# SCH_Static-stand-for-thrust-and-torque.net
KiCad netlist of a schematic drawn in EasyEDA
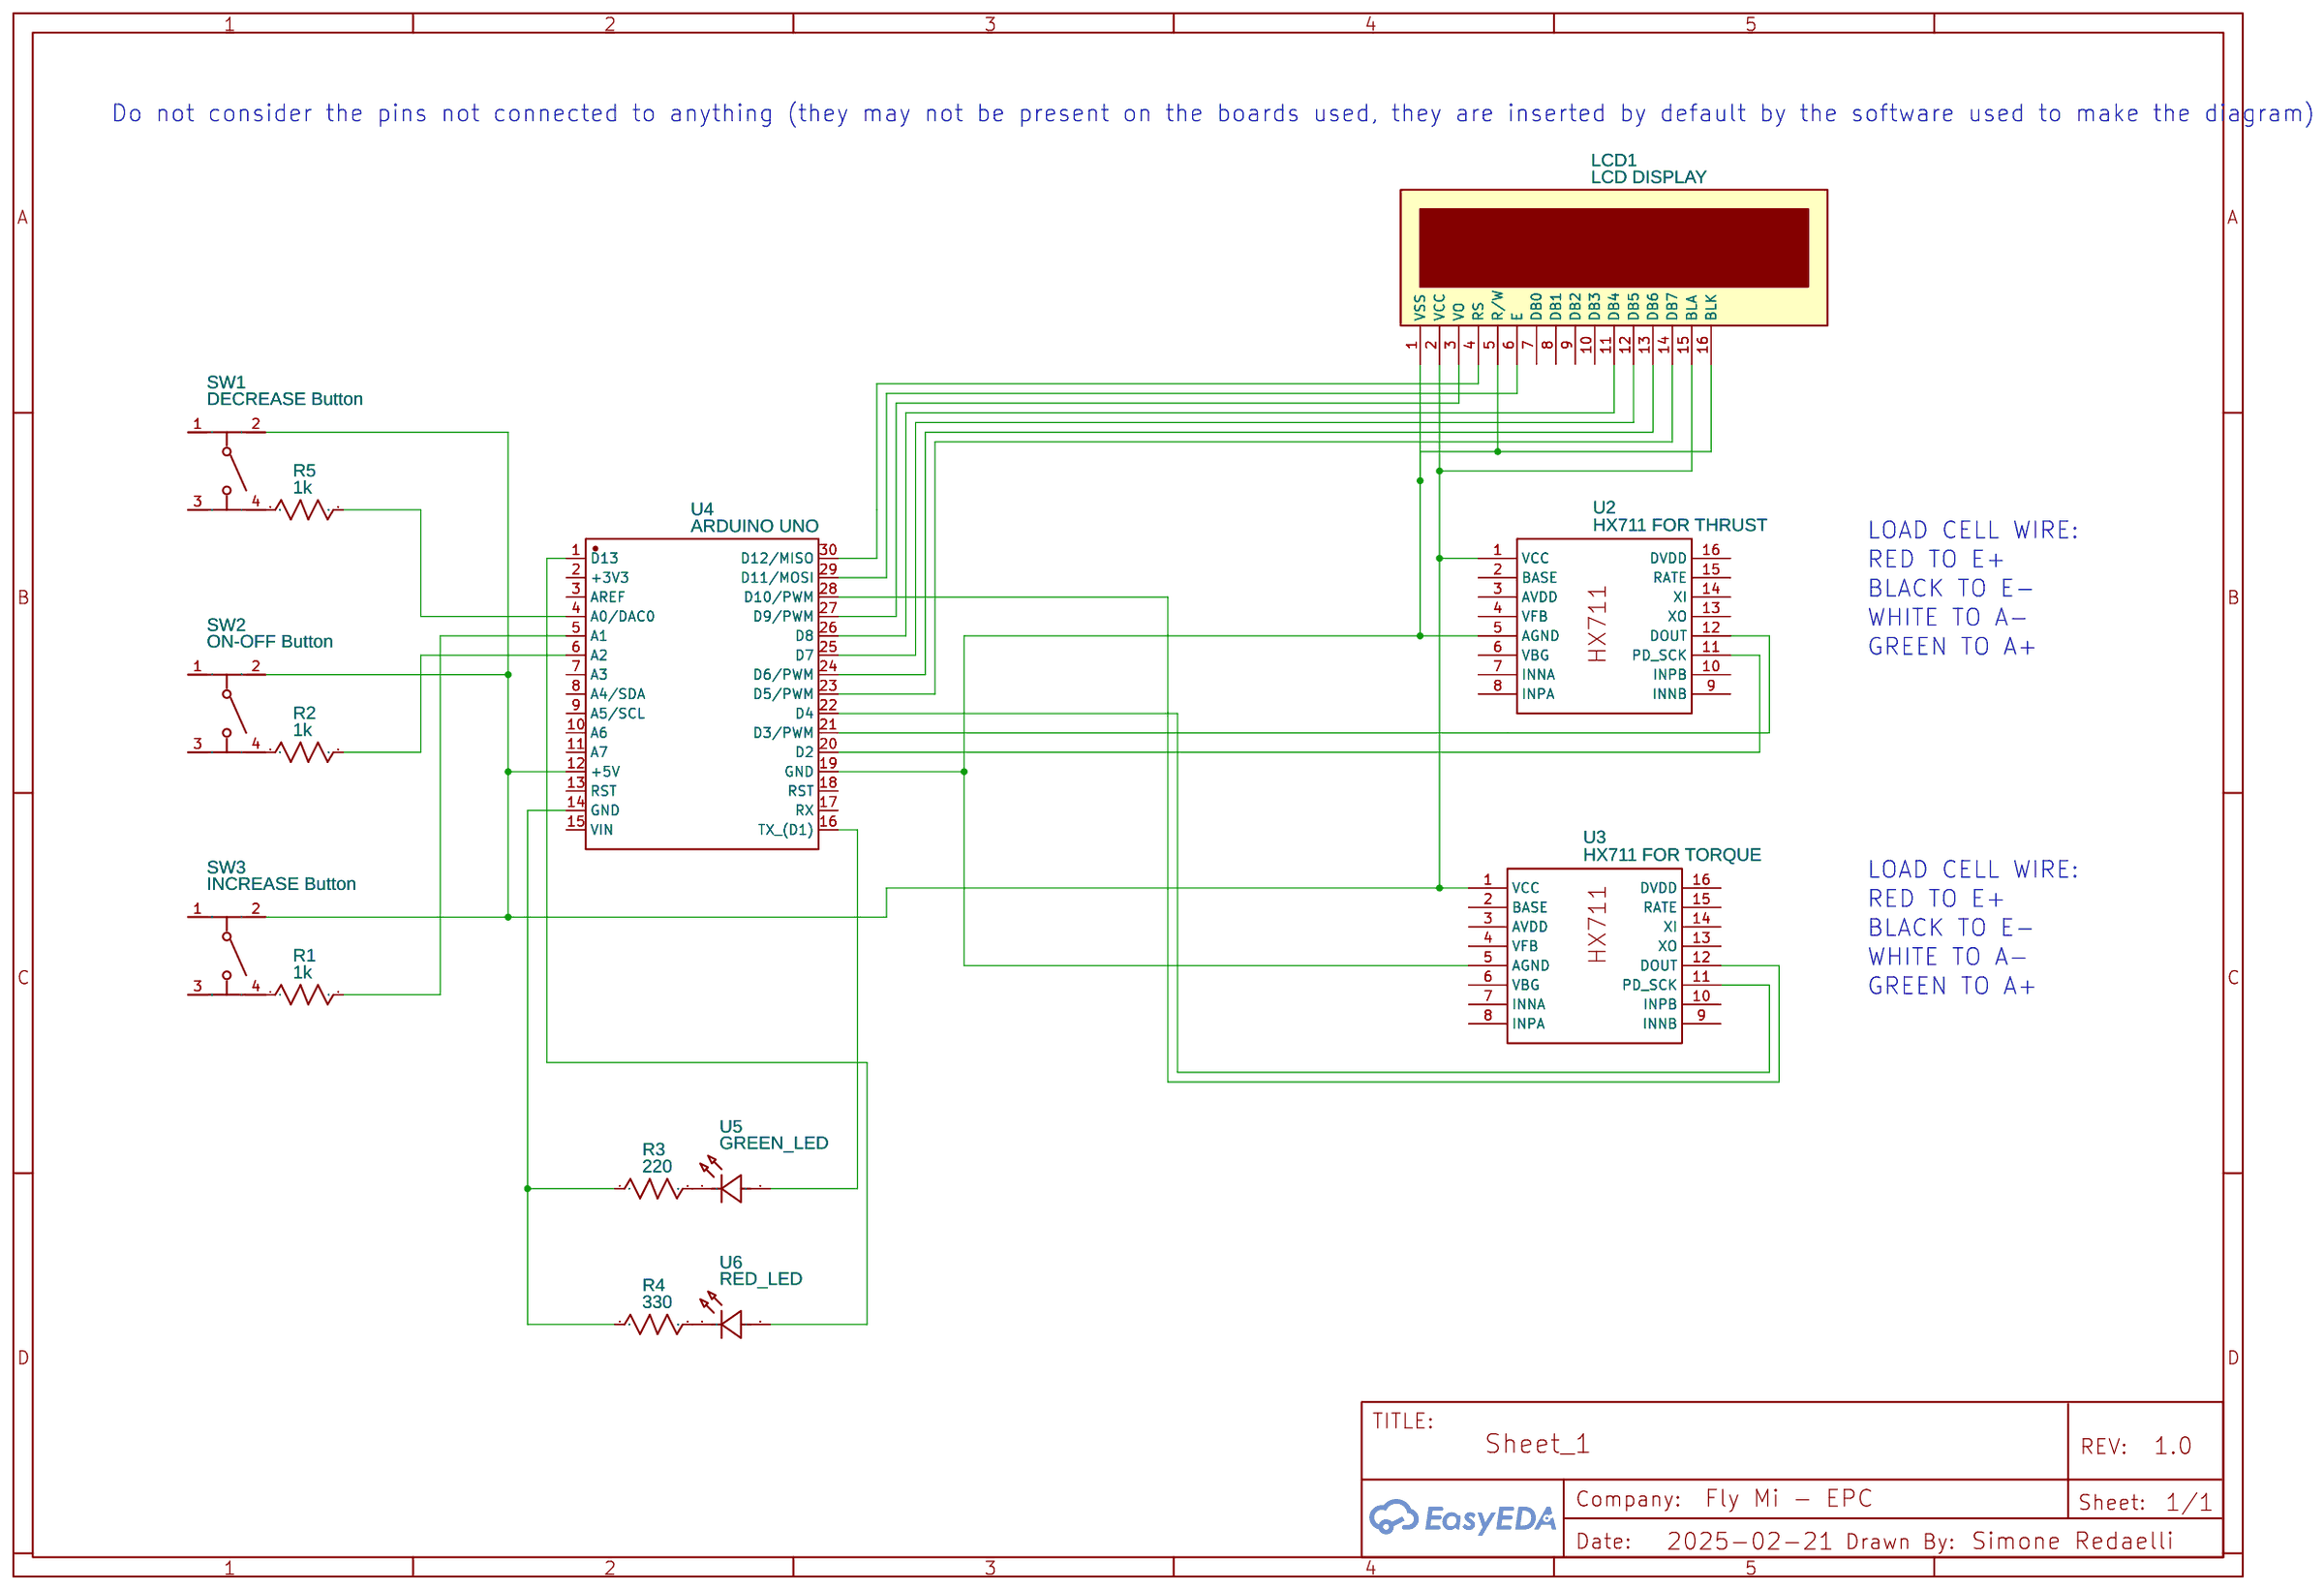
[diagram p0: schematic sheet]

(export (version "E")
  (design (tool "Eeschema 10.0.6"))
  (components
    (comp (ref "LCD1")
      (value "LCD DISPLAY")
      (fields
        (field (name "Manufacturer Part") "LCM1602K-NSW-BBW")
        (field (name "Manufacturer") "LONTECH(厦门龙特)")
      )
      (libsource (lib "") (part "LCD1602"))
    )
    (comp (ref "R1") (value "1k") (libsource (lib "") (part "R_0603_US")))
    (comp (ref "R2") (value "1k") (libsource (lib "") (part "R_0603_US")))
    (comp (ref "R3") (value "220") (libsource (lib "") (part "R_0603_US")))
    (comp (ref "R4") (value "330") (libsource (lib "") (part "R_0603_US")))
    (comp (ref "R5") (value "1k") (libsource (lib "") (part "R_0603_US")))
    (comp (ref "SW1")
      (value "DECREASE Button")
      (fields
        (field (name "Manufacturer Part") "4.5*4.5*4.8 Plastic head,260G, 0.25mm,SMD")
        (field (name "Manufacturer") "BBJ")
      )
      (libsource (lib "") (part "Button-SMD-4.5x4.5x4.8"))
    )
    (comp (ref "SW2")
      (value "ON-OFF Button")
      (fields
        (field (name "Manufacturer Part") "4.5*4.5*4.8 Plastic head,260G, 0.25mm,SMD")
        (field (name "Manufacturer") "BBJ")
      )
      (libsource (lib "") (part "Button-SMD-4.5x4.5x4.8"))
    )
    (comp (ref "SW3")
      (value "INCREASE Button")
      (fields
        (field (name "Manufacturer Part") "4.5*4.5*4.8 Plastic head,260G, 0.25mm,SMD")
        (field (name "Manufacturer") "BBJ")
      )
      (libsource (lib "") (part "Button-SMD-4.5x4.5x4.8"))
    )
    (comp (ref "U2")
      (value "HX711 FOR THRUST")
      (fields (field (name "Manufacturer Part") "HX711") (field (name "Manufacturer") "AVIA(海芯科技)"))
      (libsource (lib "") (part "HX711"))
    )
    (comp (ref "U3")
      (value "HX711 FOR TORQUE")
      (fields (field (name "Manufacturer Part") "HX711") (field (name "Manufacturer") "AVIA(海芯科技)"))
      (libsource (lib "") (part "HX711_1"))
    )
    (comp (ref "U4")
      (value "ARDUINO UNO")
      (fields (field (name "Manufacturer Part") "ABX00028") (field (name "Manufacturer") "arduino"))
      (libsource (lib "") (part "ABX00028"))
    )
    (comp (ref "U5")
      (value "GREEN_LED")
      (fields (field (name "Manufacturer Part") "0603"))
      (libsource (lib "") (part "0603"))
    )
    (comp (ref "U6")
      (value "RED_LED")
      (fields (field (name "Manufacturer Part") "0603"))
      (libsource (lib "") (part "0603"))
    )
  )
  (nets
    (net (code "1") (name "Net-(LCD1-BLA)") (class "Default")
      (node (ref "LCD1") (pin "15") (pinfunction "BLA_15") (pintype "unspecified"))
      (node (ref "LCD1") (pin "2") (pinfunction "VCC_2") (pintype "unspecified"))
      (node (ref "SW1") (pin "2") (pinfunction "2_2") (pintype "unspecified"))
      (node (ref "SW2") (pin "2") (pinfunction "2_2") (pintype "unspecified"))
      (node (ref "SW3") (pin "2") (pinfunction "2_2") (pintype "unspecified"))
      (node (ref "U2") (pin "1") (pinfunction "VCC_1") (pintype "unspecified"))
      (node (ref "U3") (pin "1") (pinfunction "VCC_1") (pintype "unspecified"))
      (node (ref "U4") (pin "12") (pinfunction "+5V_12") (pintype "unspecified"))
    )
    (net (code "2") (name "Net-(LCD1-BLK)") (class "Default")
      (node (ref "LCD1") (pin "1") (pinfunction "VSS_1") (pintype "unspecified"))
      (node (ref "LCD1") (pin "16") (pinfunction "BLK_16") (pintype "unspecified"))
      (node (ref "LCD1") (pin "5") (pinfunction "R/W_5") (pintype "unspecified"))
      (node (ref "U2") (pin "5") (pinfunction "AGND_5") (pintype "unspecified"))
      (node (ref "U3") (pin "5") (pinfunction "AGND_5") (pintype "unspecified"))
      (node (ref "U4") (pin "19") (pinfunction "GND_19") (pintype "unspecified"))
    )
    (net (code "3") (name "Net-(LCD1-DB4)") (class "Default")
      (node (ref "LCD1") (pin "11") (pinfunction "DB4_11") (pintype "unspecified"))
      (node (ref "U4") (pin "26") (pinfunction "D8_26") (pintype "unspecified"))
    )
    (net (code "4") (name "Net-(LCD1-DB5)") (class "Default")
      (node (ref "LCD1") (pin "12") (pinfunction "DB5_12") (pintype "unspecified"))
      (node (ref "U4") (pin "25") (pinfunction "D7_25") (pintype "unspecified"))
    )
    (net (code "5") (name "Net-(LCD1-DB6)") (class "Default")
      (node (ref "LCD1") (pin "13") (pinfunction "DB6_13") (pintype "unspecified"))
      (node (ref "U4") (pin "24") (pinfunction "D6/PWM_24") (pintype "unspecified"))
    )
    (net (code "6") (name "Net-(LCD1-DB7)") (class "Default")
      (node (ref "LCD1") (pin "14") (pinfunction "DB7_14") (pintype "unspecified"))
      (node (ref "U4") (pin "23") (pinfunction "D5/PWM_23") (pintype "unspecified"))
    )
    (net (code "7") (name "Net-(LCD1-E)") (class "Default")
      (node (ref "LCD1") (pin "6") (pinfunction "E_6") (pintype "unspecified"))
      (node (ref "U4") (pin "29") (pinfunction "D11/MOSI_29") (pintype "unspecified"))
    )
    (net (code "8") (name "Net-(LCD1-RS)") (class "Default")
      (node (ref "LCD1") (pin "4") (pinfunction "RS_4") (pintype "unspecified"))
      (node (ref "U4") (pin "30") (pinfunction "D12/MISO_30") (pintype "unspecified"))
    )
    (net (code "9") (name "Net-(LCD1-VO)") (class "Default")
      (node (ref "LCD1") (pin "3") (pinfunction "VO_3") (pintype "unspecified"))
      (node (ref "U4") (pin "27") (pinfunction "D9/PWM_27") (pintype "unspecified"))
    )
    (net (code "10") (name "Net-(R1-Pad1)") (class "Default")
      (node (ref "R1") (pin "1") (pinfunction "1_1") (pintype "unspecified"))
      (node (ref "SW3") (pin "4") (pinfunction "4_4") (pintype "unspecified"))
    )
    (net (code "11") (name "Net-(R2-Pad1)") (class "Default")
      (node (ref "R2") (pin "1") (pinfunction "1_1") (pintype "unspecified"))
      (node (ref "SW2") (pin "4") (pinfunction "4_4") (pintype "unspecified"))
    )
    (net (code "12") (name "Net-(R3-Pad1)") (class "Default")
      (node (ref "R3") (pin "1") (pinfunction "1_1") (pintype "unspecified"))
      (node (ref "R4") (pin "1") (pinfunction "1_1") (pintype "unspecified"))
      (node (ref "U4") (pin "14") (pinfunction "GND_14") (pintype "unspecified"))
    )
    (net (code "13") (name "Net-(R5-Pad1)") (class "Default")
      (node (ref "R5") (pin "1") (pinfunction "1_1") (pintype "unspecified"))
      (node (ref "SW1") (pin "4") (pinfunction "4_4") (pintype "unspecified"))
    )
    (net (code "14") (name "Net-(U2-DOUT)") (class "Default")
      (node (ref "U2") (pin "12") (pinfunction "DOUT_12") (pintype "unspecified"))
      (node (ref "U4") (pin "21") (pinfunction "D3/PWM_21") (pintype "unspecified"))
    )
    (net (code "15") (name "Net-(U2-PD_SCK)") (class "Default")
      (node (ref "U2") (pin "11") (pinfunction "PD_SCK_11") (pintype "unspecified"))
      (node (ref "U4") (pin "20") (pinfunction "D2_20") (pintype "unspecified"))
    )
    (net (code "16") (name "Net-(U3-DOUT)") (class "Default")
      (node (ref "U3") (pin "12") (pinfunction "DOUT_12") (pintype "unspecified"))
      (node (ref "U4") (pin "28") (pinfunction "D10/PWM_28") (pintype "unspecified"))
    )
    (net (code "17") (name "Net-(U3-PD_SCK)") (class "Default")
      (node (ref "U3") (pin "11") (pinfunction "PD_SCK_11") (pintype "unspecified"))
      (node (ref "U4") (pin "22") (pinfunction "D4_22") (pintype "unspecified"))
    )
    (net (code "18") (name "Net-(U4-A0{slash}DAC0)") (class "Default")
      (node (ref "R5") (pin "2") (pinfunction "2_2") (pintype "unspecified"))
      (node (ref "U4") (pin "4") (pinfunction "A0/DAC0_4") (pintype "unspecified"))
    )
    (net (code "19") (name "Net-(U4-A1)") (class "Default")
      (node (ref "R1") (pin "2") (pinfunction "2_2") (pintype "unspecified"))
      (node (ref "U4") (pin "5") (pinfunction "A1_5") (pintype "unspecified"))
    )
    (net (code "20") (name "Net-(U4-A2)") (class "Default")
      (node (ref "R2") (pin "2") (pinfunction "2_2") (pintype "unspecified"))
      (node (ref "U4") (pin "6") (pinfunction "A2_6") (pintype "unspecified"))
    )
    (net (code "21") (name "Net-(U4-D13)") (class "Default")
      (node (ref "U4") (pin "1") (pinfunction "D13_1") (pintype "unspecified"))
      (node (ref "U6") (pin "2") (pinfunction "A_2") (pintype "unspecified"))
    )
    (net (code "22") (name "Net-(U4-TX_(D1))") (class "Default")
      (node (ref "U4") (pin "16") (pinfunction "TX_(D1)_16") (pintype "unspecified"))
      (node (ref "U5") (pin "2") (pinfunction "A_2") (pintype "unspecified"))
    )
    (net (code "23") (name "Net-(U5-K)") (class "Default")
      (node (ref "R3") (pin "2") (pinfunction "2_2") (pintype "unspecified"))
      (node (ref "U5") (pin "1") (pinfunction "K_1") (pintype "unspecified"))
    )
    (net (code "24") (name "Net-(U6-K)") (class "Default")
      (node (ref "R4") (pin "2") (pinfunction "2_2") (pintype "unspecified"))
      (node (ref "U6") (pin "1") (pinfunction "K_1") (pintype "unspecified"))
    )
    (net (code "25") (name "unconnected-(LCD1-DB0-Pad7)") (class "Default")
      (node (ref "LCD1") (pin "7") (pinfunction "DB0_7") (pintype "unspecified"))
    )
    (net (code "26") (name "unconnected-(LCD1-DB1-Pad8)") (class "Default")
      (node (ref "LCD1") (pin "8") (pinfunction "DB1_8") (pintype "unspecified"))
    )
    (net (code "27") (name "unconnected-(LCD1-DB2-Pad9)") (class "Default")
      (node (ref "LCD1") (pin "9") (pinfunction "DB2_9") (pintype "unspecified"))
    )
    (net (code "28") (name "unconnected-(LCD1-DB3-Pad10)") (class "Default")
      (node (ref "LCD1") (pin "10") (pinfunction "DB3_10") (pintype "unspecified"))
    )
    (net (code "29") (name "unconnected-(SW1-Pad1)") (class "Default")
      (node (ref "SW1") (pin "1") (pinfunction "1_1") (pintype "unspecified"))
    )
    (net (code "30") (name "unconnected-(SW1-Pad3)") (class "Default")
      (node (ref "SW1") (pin "3") (pinfunction "3_3") (pintype "unspecified"))
    )
    (net (code "31") (name "unconnected-(SW2-Pad1)") (class "Default")
      (node (ref "SW2") (pin "1") (pinfunction "1_1") (pintype "unspecified"))
    )
    (net (code "32") (name "unconnected-(SW2-Pad3)") (class "Default")
      (node (ref "SW2") (pin "3") (pinfunction "3_3") (pintype "unspecified"))
    )
    (net (code "33") (name "unconnected-(SW3-Pad1)") (class "Default")
      (node (ref "SW3") (pin "1") (pinfunction "1_1") (pintype "unspecified"))
    )
    (net (code "34") (name "unconnected-(SW3-Pad3)") (class "Default")
      (node (ref "SW3") (pin "3") (pinfunction "3_3") (pintype "unspecified"))
    )
    (net (code "35") (name "unconnected-(U2-AVDD-Pad3)") (class "Default")
      (node (ref "U2") (pin "3") (pinfunction "AVDD_3") (pintype "unspecified"))
    )
    (net (code "36") (name "unconnected-(U2-BASE-Pad2)") (class "Default")
      (node (ref "U2") (pin "2") (pinfunction "BASE_2") (pintype "unspecified"))
    )
    (net (code "37") (name "unconnected-(U2-DVDD-Pad16)") (class "Default")
      (node (ref "U2") (pin "16") (pinfunction "DVDD_16") (pintype "unspecified"))
    )
    (net (code "38") (name "unconnected-(U2-INNA-Pad7)") (class "Default")
      (node (ref "U2") (pin "7") (pinfunction "INNA_7") (pintype "unspecified"))
    )
    (net (code "39") (name "unconnected-(U2-INNB-Pad9)") (class "Default")
      (node (ref "U2") (pin "9") (pinfunction "INNB_9") (pintype "unspecified"))
    )
    (net (code "40") (name "unconnected-(U2-INPA-Pad8)") (class "Default")
      (node (ref "U2") (pin "8") (pinfunction "INPA_8") (pintype "unspecified"))
    )
    (net (code "41") (name "unconnected-(U2-INPB-Pad10)") (class "Default")
      (node (ref "U2") (pin "10") (pinfunction "INPB_10") (pintype "unspecified"))
    )
    (net (code "42") (name "unconnected-(U2-RATE-Pad15)") (class "Default")
      (node (ref "U2") (pin "15") (pinfunction "RATE_15") (pintype "unspecified"))
    )
    (net (code "43") (name "unconnected-(U2-VBG-Pad6)") (class "Default")
      (node (ref "U2") (pin "6") (pinfunction "VBG_6") (pintype "unspecified"))
    )
    (net (code "44") (name "unconnected-(U2-VFB-Pad4)") (class "Default")
      (node (ref "U2") (pin "4") (pinfunction "VFB_4") (pintype "unspecified"))
    )
    (net (code "45") (name "unconnected-(U2-XI-Pad14)") (class "Default")
      (node (ref "U2") (pin "14") (pinfunction "XI_14") (pintype "unspecified"))
    )
    (net (code "46") (name "unconnected-(U2-XO-Pad13)") (class "Default")
      (node (ref "U2") (pin "13") (pinfunction "XO_13") (pintype "unspecified"))
    )
    (net (code "47") (name "unconnected-(U3-AVDD-Pad3)") (class "Default")
      (node (ref "U3") (pin "3") (pinfunction "AVDD_3") (pintype "unspecified"))
    )
    (net (code "48") (name "unconnected-(U3-BASE-Pad2)") (class "Default")
      (node (ref "U3") (pin "2") (pinfunction "BASE_2") (pintype "unspecified"))
    )
    (net (code "49") (name "unconnected-(U3-DVDD-Pad16)") (class "Default")
      (node (ref "U3") (pin "16") (pinfunction "DVDD_16") (pintype "unspecified"))
    )
    (net (code "50") (name "unconnected-(U3-INNA-Pad7)") (class "Default")
      (node (ref "U3") (pin "7") (pinfunction "INNA_7") (pintype "unspecified"))
    )
    (net (code "51") (name "unconnected-(U3-INNB-Pad9)") (class "Default")
      (node (ref "U3") (pin "9") (pinfunction "INNB_9") (pintype "unspecified"))
    )
    (net (code "52") (name "unconnected-(U3-INPA-Pad8)") (class "Default")
      (node (ref "U3") (pin "8") (pinfunction "INPA_8") (pintype "unspecified"))
    )
    (net (code "53") (name "unconnected-(U3-INPB-Pad10)") (class "Default")
      (node (ref "U3") (pin "10") (pinfunction "INPB_10") (pintype "unspecified"))
    )
    (net (code "54") (name "unconnected-(U3-RATE-Pad15)") (class "Default")
      (node (ref "U3") (pin "15") (pinfunction "RATE_15") (pintype "unspecified"))
    )
    (net (code "55") (name "unconnected-(U3-VBG-Pad6)") (class "Default")
      (node (ref "U3") (pin "6") (pinfunction "VBG_6") (pintype "unspecified"))
    )
    (net (code "56") (name "unconnected-(U3-VFB-Pad4)") (class "Default")
      (node (ref "U3") (pin "4") (pinfunction "VFB_4") (pintype "unspecified"))
    )
    (net (code "57") (name "unconnected-(U3-XI-Pad14)") (class "Default")
      (node (ref "U3") (pin "14") (pinfunction "XI_14") (pintype "unspecified"))
    )
    (net (code "58") (name "unconnected-(U3-XO-Pad13)") (class "Default")
      (node (ref "U3") (pin "13") (pinfunction "XO_13") (pintype "unspecified"))
    )
    (net (code "59") (name "unconnected-(U4-+3V3-Pad2)") (class "Default")
      (node (ref "U4") (pin "2") (pinfunction "+3V3_2") (pintype "unspecified"))
    )
    (net (code "60") (name "unconnected-(U4-A3-Pad7)") (class "Default")
      (node (ref "U4") (pin "7") (pinfunction "A3_7") (pintype "unspecified"))
    )
    (net (code "61") (name "unconnected-(U4-A4{slash}SDA-Pad8)") (class "Default")
      (node (ref "U4") (pin "8") (pinfunction "A4/SDA_8") (pintype "unspecified"))
    )
    (net (code "62") (name "unconnected-(U4-A5{slash}SCL-Pad9)") (class "Default")
      (node (ref "U4") (pin "9") (pinfunction "A5/SCL_9") (pintype "unspecified"))
    )
    (net (code "63") (name "unconnected-(U4-A6-Pad10)") (class "Default")
      (node (ref "U4") (pin "10") (pinfunction "A6_10") (pintype "unspecified"))
    )
    (net (code "64") (name "unconnected-(U4-A7-Pad11)") (class "Default")
      (node (ref "U4") (pin "11") (pinfunction "A7_11") (pintype "unspecified"))
    )
    (net (code "65") (name "unconnected-(U4-AREF-Pad3)") (class "Default")
      (node (ref "U4") (pin "3") (pinfunction "AREF_3") (pintype "unspecified"))
    )
    (net (code "66") (name "unconnected-(U4-RST-Pad13)") (class "Default")
      (node (ref "U4") (pin "13") (pinfunction "RST_13") (pintype "unspecified"))
    )
    (net (code "67") (name "unconnected-(U4-RST-Pad18)") (class "Default")
      (node (ref "U4") (pin "18") (pinfunction "RST_18") (pintype "unspecified"))
    )
    (net (code "68") (name "unconnected-(U4-RX-Pad17)") (class "Default")
      (node (ref "U4") (pin "17") (pinfunction "RX_17") (pintype "unspecified"))
    )
    (net (code "69") (name "unconnected-(U4-VIN-Pad15)") (class "Default")
      (node (ref "U4") (pin "15") (pinfunction "VIN_15") (pintype "unspecified"))
    )
  )
)
